# Adafruit_BNO08x.net
KiCad netlist of a schematic drawn in EAGLE
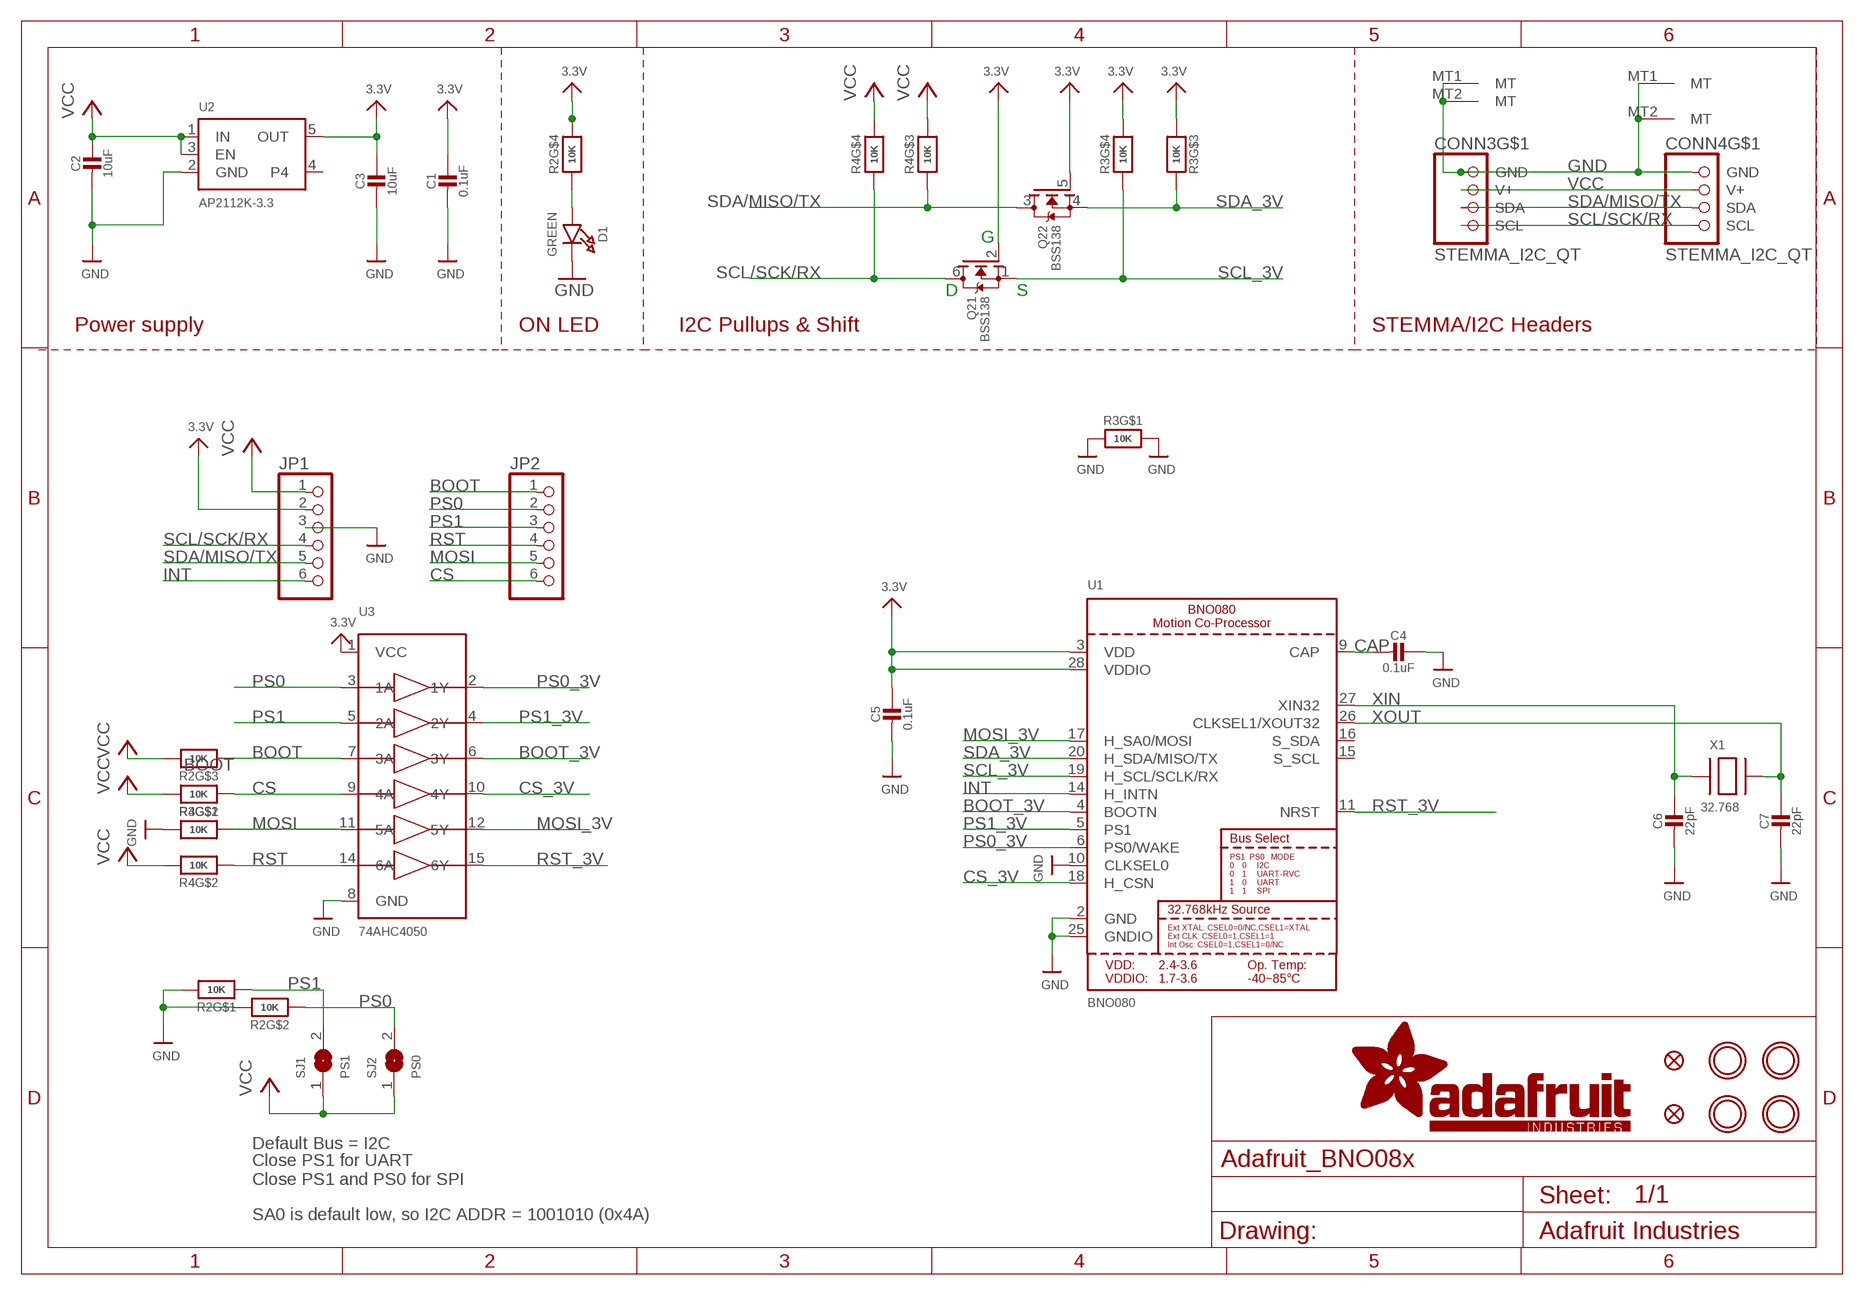
[diagram p0: schematic, sheet 1]

(export (version "E")
  (design (tool "Eeschema 10.0.6"))
  (components
    (comp (ref "C1")
      (value "0.1uF")
      (footprint "eagle-import:0603-NO")
      (libsource (lib "eagle-import") (part "CAP_CERAMIC0603_NO"))
    )
    (comp (ref "C2")
      (value "10uF")
      (footprint "eagle-import:0805-NO")
      (libsource (lib "eagle-import") (part "CAP_CERAMIC0805-NOOUTLINE"))
    )
    (comp (ref "C3")
      (value "10uF")
      (footprint "eagle-import:0805-NO")
      (libsource (lib "eagle-import") (part "CAP_CERAMIC0805-NOOUTLINE"))
    )
    (comp (ref "C4")
      (value "0.1uF")
      (footprint "eagle-import:0603-NO")
      (libsource (lib "eagle-import") (part "CAP_CERAMIC0603_NO"))
    )
    (comp (ref "C5")
      (value "0.1uF")
      (footprint "eagle-import:0603-NO")
      (libsource (lib "eagle-import") (part "CAP_CERAMIC0603_NO"))
    )
    (comp (ref "C6")
      (value "22pF")
      (footprint "eagle-import:0603-NO")
      (libsource (lib "eagle-import") (part "CAP_CERAMIC0603_NO"))
    )
    (comp (ref "C7")
      (value "22pF")
      (footprint "eagle-import:0603-NO")
      (libsource (lib "eagle-import") (part "CAP_CERAMIC0603_NO"))
    )
    (comp (ref "CONN3")
      (value "STEMMA_I2C_QT")
      (footprint "eagle-import:JST_SH4")
      (libsource (lib "eagle-import") (part "STEMMA_I2C_QT"))
    )
    (comp (ref "CONN4")
      (value "STEMMA_I2C_QT")
      (footprint "eagle-import:JST_SH4")
      (libsource (lib "eagle-import") (part "STEMMA_I2C_QT"))
    )
    (comp (ref "D1")
      (value "GREEN")
      (footprint "eagle-import:CHIPLED_0603_NOOUTLINE")
      (libsource (lib "eagle-import") (part "LED0603_NOOUTLINE"))
    )
    (comp (ref "FID3")
      (value "FIDUCIAL_1MM")
      (footprint "eagle-import:FIDUCIAL_1MM")
      (libsource (lib "eagle-import") (part "FIDUCIAL_1MM"))
    )
    (comp (ref "FID4")
      (value "FIDUCIAL_1MM")
      (footprint "eagle-import:FIDUCIAL_1MM")
      (libsource (lib "eagle-import") (part "FIDUCIAL_1MM"))
    )
    (comp (ref "JP1")
      (value "HEADER-1X670MIL")
      (footprint "eagle-import:1X06_ROUND_70")
      (libsource (lib "eagle-import") (part "HEADER-1X670MIL"))
    )
    (comp (ref "JP2")
      (value "HEADER-1X670MIL")
      (footprint "eagle-import:1X06_ROUND_70")
      (libsource (lib "eagle-import") (part "HEADER-1X670MIL"))
    )
    (comp (ref "Q2")
      (value "BSS138")
      (footprint "eagle-import:SOT363")
      (libsource (lib "eagle-import") (part "MOSFET-N_DUAL"))
    )
    (comp (ref "R2")
      (value "10K")
      (footprint "eagle-import:RESPACK_4X0603")
      (libsource (lib "eagle-import") (part "RESISTOR_4PACK"))
    )
    (comp (ref "R3")
      (value "10K")
      (footprint "eagle-import:RESPACK_4X0603")
      (libsource (lib "eagle-import") (part "RESISTOR_4PACK"))
    )
    (comp (ref "R4")
      (value "10K")
      (footprint "eagle-import:RESPACK_4X0603")
      (libsource (lib "eagle-import") (part "RESISTOR_4PACK"))
    )
    (comp (ref "SJ1")
      (value "PS1")
      (footprint "eagle-import:SOLDERJUMPER_ARROW_NOPASTE")
      (libsource (lib "eagle-import") (part "SOLDERJUMPER"))
    )
    (comp (ref "SJ2")
      (value "PS0")
      (footprint "eagle-import:SOLDERJUMPER_ARROW_NOPASTE")
      (libsource (lib "eagle-import") (part "SOLDERJUMPER"))
    )
    (comp (ref "U$1")
      (value "MOUNTINGHOLE2.5")
      (footprint "eagle-import:MOUNTINGHOLE_2.5_PLATED")
      (libsource (lib "eagle-import") (part "MOUNTINGHOLE2.5"))
    )
    (comp (ref "U$17")
      (value "MOUNTINGHOLE2.5")
      (footprint "eagle-import:MOUNTINGHOLE_2.5_PLATED")
      (libsource (lib "eagle-import") (part "MOUNTINGHOLE2.5"))
    )
    (comp (ref "U$19")
      (value "MOUNTINGHOLE2.5")
      (footprint "eagle-import:MOUNTINGHOLE_2.5_PLATED")
      (libsource (lib "eagle-import") (part "MOUNTINGHOLE2.5"))
    )
    (comp (ref "U$21")
      (value "MOUNTINGHOLE2.5")
      (footprint "eagle-import:MOUNTINGHOLE_2.5_PLATED")
      (libsource (lib "eagle-import") (part "MOUNTINGHOLE2.5"))
    )
    (comp (ref "U1")
      (value "BNO080")
      (footprint "eagle-import:BNO080")
      (libsource (lib "eagle-import") (part "BNO080"))
    )
    (comp (ref "U2")
      (value "AP2112K-3.3")
      (footprint "eagle-import:SOT23-5")
      (libsource (lib "eagle-import") (part "VREG_SOT23-5"))
    )
    (comp (ref "U3")
      (value "74AHC4050")
      (footprint "eagle-import:TSSOP16")
      (libsource (lib "eagle-import") (part "74HC4050DTSSOP"))
    )
    (comp (ref "X1")
      (value "32.768")
      (footprint "eagle-import:XTAL3215")
      (libsource (lib "eagle-import") (part "XTAL-3.2X1.5"))
    )
  )
  (nets
    (net (code "1") (name "/BOOT") (class "Default")
      (node (ref "JP2") (pin "1") (pinfunction "1_1") (pintype "passive"))
      (node (ref "R2") (pin "3") (pinfunction "1_3") (pintype "passive"))
      (node (ref "U3") (pin "7") (pinfunction "3A_7") (pintype "bidirectional"))
    )
    (net (code "2") (name "/BOOT_3V") (class "Default")
      (node (ref "U1") (pin "4") (pinfunction "BOOTN_4") (pintype "input"))
      (node (ref "U3") (pin "6") (pinfunction "3Y_6") (pintype "bidirectional"))
    )
    (net (code "3") (name "/CAP") (class "Default")
      (node (ref "C4") (pin "2") (pinfunction "2_2") (pintype "passive"))
      (node (ref "U1") (pin "9") (pinfunction "CAP_9") (pintype "passive"))
    )
    (net (code "4") (name "/CS") (class "Default")
      (node (ref "JP2") (pin "6") (pinfunction "6_6") (pintype "passive"))
      (node (ref "R4") (pin "1") (pinfunction "1_1") (pintype "passive"))
      (node (ref "U3") (pin "9") (pinfunction "4A_9") (pintype "bidirectional"))
    )
    (net (code "5") (name "/CS_3V") (class "Default")
      (node (ref "U1") (pin "18") (pinfunction "H_CSN_18") (pintype "input"))
      (node (ref "U3") (pin "10") (pinfunction "4Y_10") (pintype "bidirectional"))
    )
    (net (code "6") (name "/INT") (class "Default")
      (node (ref "JP1") (pin "6") (pinfunction "6_6") (pintype "passive"))
      (node (ref "U1") (pin "14") (pinfunction "H_INTN_14") (pintype "output"))
    )
    (net (code "7") (name "/MOSI") (class "Default")
      (node (ref "JP2") (pin "5") (pinfunction "5_5") (pintype "passive"))
      (node (ref "R3") (pin "7") (pinfunction "2_7") (pintype "passive"))
      (node (ref "U3") (pin "11") (pinfunction "5A_11") (pintype "bidirectional"))
    )
    (net (code "8") (name "/MOSI_3V") (class "Default")
      (node (ref "U1") (pin "17") (pinfunction "H_SA0/MOSI_17") (pintype "output"))
      (node (ref "U3") (pin "12") (pinfunction "5Y_12") (pintype "bidirectional"))
    )
    (net (code "9") (name "/PS0") (class "Default")
      (node (ref "JP2") (pin "2") (pinfunction "2_2") (pintype "passive"))
      (node (ref "R2") (pin "2") (pinfunction "1_2") (pintype "passive"))
      (node (ref "SJ2") (pin "2") (pinfunction "2_2") (pintype "passive"))
      (node (ref "U3") (pin "3") (pinfunction "1A_3") (pintype "bidirectional"))
    )
    (net (code "10") (name "/PS0_3V") (class "Default")
      (node (ref "U1") (pin "6") (pinfunction "PS0/WAKE_6") (pintype "input"))
      (node (ref "U3") (pin "2") (pinfunction "1Y_2") (pintype "bidirectional"))
    )
    (net (code "11") (name "/PS1") (class "Default")
      (node (ref "JP2") (pin "3") (pinfunction "3_3") (pintype "passive"))
      (node (ref "R2") (pin "1") (pinfunction "1_1") (pintype "passive"))
      (node (ref "SJ1") (pin "2") (pinfunction "2_2") (pintype "passive"))
      (node (ref "U3") (pin "5") (pinfunction "2A_5") (pintype "bidirectional"))
    )
    (net (code "12") (name "/PS1_3V") (class "Default")
      (node (ref "U1") (pin "5") (pinfunction "PS1_5") (pintype "input"))
      (node (ref "U3") (pin "4") (pinfunction "2Y_4") (pintype "bidirectional"))
    )
    (net (code "13") (name "/RST") (class "Default")
      (node (ref "JP2") (pin "4") (pinfunction "4_4") (pintype "passive"))
      (node (ref "R4") (pin "2") (pinfunction "1_2") (pintype "passive"))
      (node (ref "U3") (pin "14") (pinfunction "6A_14") (pintype "bidirectional"))
    )
    (net (code "14") (name "/RST_3V") (class "Default")
      (node (ref "U1") (pin "11") (pinfunction "NRST_11") (pintype "input"))
      (node (ref "U3") (pin "15") (pinfunction "6Y_15") (pintype "bidirectional"))
    )
    (net (code "15") (name "/SCL_3V") (class "Default")
      (node (ref "Q2") (pin "1") (pinfunction "S_1") (pintype "bidirectional"))
      (node (ref "R3") (pin "4") (pinfunction "1_4") (pintype "passive"))
      (node (ref "U1") (pin "19") (pinfunction "H_SCL/SCLK/RX_19") (pintype "bidirectional"))
    )
    (net (code "16") (name "/SCL{slash}SCK{slash}RX") (class "Default")
      (node (ref "CONN3") (pin "4") (pinfunction "SCL_4") (pintype "passive"))
      (node (ref "CONN4") (pin "4") (pinfunction "SCL_4") (pintype "passive"))
      (node (ref "JP1") (pin "4") (pinfunction "4_4") (pintype "passive"))
      (node (ref "Q2") (pin "6") (pinfunction "D_6") (pintype "bidirectional"))
      (node (ref "R4") (pin "4") (pinfunction "1_4") (pintype "passive"))
    )
    (net (code "17") (name "/SDA_3V") (class "Default")
      (node (ref "Q2") (pin "4") (pinfunction "S_4") (pintype "bidirectional"))
      (node (ref "R3") (pin "6") (pinfunction "2_6") (pintype "passive"))
      (node (ref "U1") (pin "20") (pinfunction "H_SDA/MISO/TX_20") (pintype "bidirectional"))
    )
    (net (code "18") (name "/SDA{slash}MISO{slash}TX") (class "Default")
      (node (ref "CONN3") (pin "3") (pinfunction "SDA_3") (pintype "passive"))
      (node (ref "CONN4") (pin "3") (pinfunction "SDA_3") (pintype "passive"))
      (node (ref "JP1") (pin "5") (pinfunction "5_5") (pintype "passive"))
      (node (ref "Q2") (pin "3") (pinfunction "D_3") (pintype "bidirectional"))
      (node (ref "R4") (pin "3") (pinfunction "1_3") (pintype "passive"))
    )
    (net (code "19") (name "/XIN") (class "Default")
      (node (ref "C6") (pin "1") (pinfunction "1_1") (pintype "passive"))
      (node (ref "U1") (pin "27") (pinfunction "XIN32_27") (pintype "input"))
      (node (ref "X1") (pin "P$1") (pinfunction "P$1_P$1") (pintype "bidirectional"))
    )
    (net (code "20") (name "/XOUT") (class "Default")
      (node (ref "C7") (pin "1") (pinfunction "1_1") (pintype "passive"))
      (node (ref "U1") (pin "26") (pinfunction "CLKSEL1/XOUT32_26") (pintype "output"))
      (node (ref "X1") (pin "P$2") (pinfunction "P$2_P$2") (pintype "bidirectional"))
    )
    (net (code "21") (name "3.3V") (class "Default")
      (node (ref "C1") (pin "1") (pinfunction "1_1") (pintype "passive"))
      (node (ref "C3") (pin "1") (pinfunction "1_1") (pintype "passive"))
      (node (ref "C5") (pin "1") (pinfunction "1_1") (pintype "passive"))
      (node (ref "JP1") (pin "2") (pinfunction "2_2") (pintype "passive"))
      (node (ref "Q2") (pin "2") (pinfunction "G_2") (pintype "bidirectional"))
      (node (ref "Q2") (pin "5") (pinfunction "G_5") (pintype "bidirectional"))
      (node (ref "R2") (pin "5") (pinfunction "2_5") (pintype "passive"))
      (node (ref "R3") (pin "3") (pinfunction "1_3") (pintype "passive"))
      (node (ref "R3") (pin "5") (pinfunction "2_5") (pintype "passive"))
      (node (ref "U1") (pin "28") (pinfunction "VDDIO_28") (pintype "power_in"))
      (node (ref "U1") (pin "3") (pinfunction "VDD_3") (pintype "power_in"))
      (node (ref "U2") (pin "5") (pinfunction "OUT_5") (pintype "power_in"))
      (node (ref "U3") (pin "1") (pinfunction "VCC_1") (pintype "bidirectional"))
    )
    (net (code "22") (name "GND") (class "Default")
      (node (ref "C1") (pin "2") (pinfunction "2_2") (pintype "passive"))
      (node (ref "C2") (pin "2") (pinfunction "2_2") (pintype "passive"))
      (node (ref "C3") (pin "2") (pinfunction "2_2") (pintype "passive"))
      (node (ref "C4") (pin "1") (pinfunction "1_1") (pintype "passive"))
      (node (ref "C5") (pin "2") (pinfunction "2_2") (pintype "passive"))
      (node (ref "C6") (pin "2") (pinfunction "2_2") (pintype "passive"))
      (node (ref "C7") (pin "2") (pinfunction "2_2") (pintype "passive"))
      (node (ref "CONN3") (pin "1") (pinfunction "GND_1") (pintype "passive"))
      (node (ref "CONN3") (pin "MT1") (pinfunction "MT_MT1") (pintype "bidirectional"))
      (node (ref "CONN3") (pin "MT2") (pinfunction "MT_MT2") (pintype "bidirectional"))
      (node (ref "CONN4") (pin "1") (pinfunction "GND_1") (pintype "passive"))
      (node (ref "CONN4") (pin "MT1") (pinfunction "MT_MT1") (pintype "bidirectional"))
      (node (ref "CONN4") (pin "MT2") (pinfunction "MT_MT2") (pintype "bidirectional"))
      (node (ref "D1") (pin "C") (pinfunction "C_C") (pintype "passive"))
      (node (ref "JP1") (pin "3") (pinfunction "3_3") (pintype "passive"))
      (node (ref "R2") (pin "7") (pinfunction "2_7") (pintype "passive"))
      (node (ref "R2") (pin "8") (pinfunction "2_8") (pintype "passive"))
      (node (ref "R3") (pin "1") (pinfunction "1_1") (pintype "passive"))
      (node (ref "R3") (pin "2") (pinfunction "1_2") (pintype "passive"))
      (node (ref "R3") (pin "8") (pinfunction "2_8") (pintype "passive"))
      (node (ref "U1") (pin "10") (pinfunction "CLKSEL0_10") (pintype "input"))
      (node (ref "U1") (pin "2") (pinfunction "GND_2") (pintype "power_in"))
      (node (ref "U1") (pin "25") (pinfunction "GNDIO_25") (pintype "power_in"))
      (node (ref "U2") (pin "2") (pinfunction "GND_2") (pintype "power_in"))
      (node (ref "U3") (pin "8") (pinfunction "GND_8") (pintype "bidirectional"))
    )
    (net (code "23") (name "Net-(R2D-1)") (class "Default")
      (node (ref "D1") (pin "A") (pinfunction "A_A") (pintype "passive"))
      (node (ref "R2") (pin "4") (pinfunction "1_4") (pintype "passive"))
    )
    (net (code "24") (name "VCC") (class "Default")
      (node (ref "C2") (pin "1") (pinfunction "1_1") (pintype "passive"))
      (node (ref "CONN3") (pin "2") (pinfunction "V+_2") (pintype "passive"))
      (node (ref "CONN4") (pin "2") (pinfunction "V+_2") (pintype "passive"))
      (node (ref "JP1") (pin "1") (pinfunction "1_1") (pintype "passive"))
      (node (ref "R2") (pin "6") (pinfunction "2_6") (pintype "passive"))
      (node (ref "R4") (pin "5") (pinfunction "2_5") (pintype "passive"))
      (node (ref "R4") (pin "6") (pinfunction "2_6") (pintype "passive"))
      (node (ref "R4") (pin "7") (pinfunction "2_7") (pintype "passive"))
      (node (ref "R4") (pin "8") (pinfunction "2_8") (pintype "passive"))
      (node (ref "SJ1") (pin "1") (pinfunction "1_1") (pintype "passive"))
      (node (ref "SJ2") (pin "1") (pinfunction "1_1") (pintype "passive"))
      (node (ref "U2") (pin "1") (pinfunction "IN_1") (pintype "power_in"))
      (node (ref "U2") (pin "3") (pinfunction "EN_3") (pintype "input"))
    )
    (net (code "25") (name "unconnected-(U1-S_SCL-Pad15)") (class "Default")
      (node (ref "U1") (pin "15") (pinfunction "S_SCL_15") (pintype "bidirectional"))
    )
    (net (code "26") (name "unconnected-(U1-S_SDA-Pad16)") (class "Default")
      (node (ref "U1") (pin "16") (pinfunction "S_SDA_16") (pintype "bidirectional"))
    )
    (net (code "27") (name "unconnected-(U2-P4-Pad4)") (class "Default")
      (node (ref "U2") (pin "4") (pinfunction "P4_4") (pintype "bidirectional"))
    )
  )
)
